# CCLights.net
KiCad netlist of a schematic drawn in Altium Designer
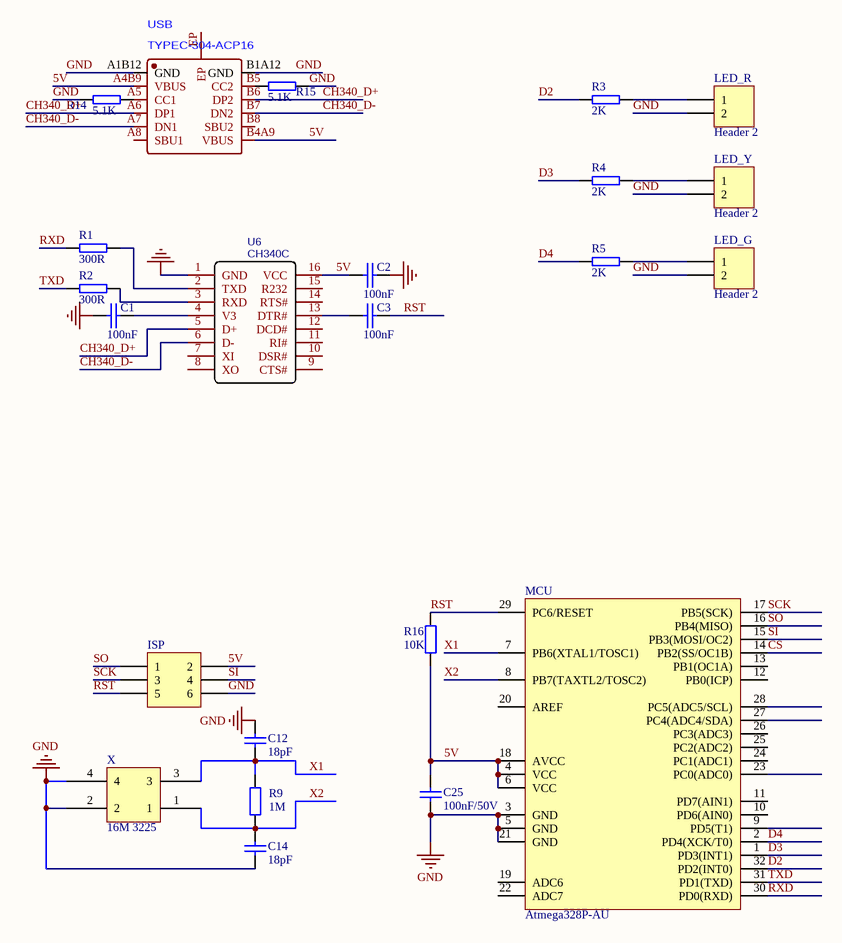
[diagram p0: CCLights.schdoc]

(export (version "E")
  (design (tool "Eeschema 10.0.6"))
  (components
    (comp (ref "C1")
      (value "100nF")
      (footprint "Miscellaneous Devices LC:LC-0603_C")
      (description "Capacitor")
      (libsource (lib "*") (part "CAP"))
    )
    (comp (ref "C2")
      (value "100nF")
      (footprint "Miscellaneous Devices LC:LC-0603_C")
      (description "Capacitor")
      (libsource (lib "*") (part "CAP"))
    )
    (comp (ref "C3")
      (value "100nF")
      (footprint "Miscellaneous Devices LC:LC-0603_C")
      (description "Capacitor")
      (libsource (lib "*") (part "CAP"))
    )
    (comp (ref "C12")
      (value "18pF")
      (footprint "0603C")
      (description "Capacitor")
      (fields (field (name "PUBLISHER") "Altium Limited"))
      (libsource (lib "Miscellaneous Devices") (part "Cap"))
    )
    (comp (ref "C14")
      (value "18pF")
      (footprint "0603C")
      (description "Capacitor")
      (fields (field (name "PUBLISHER") "Altium Limited"))
      (libsource (lib "Miscellaneous Devices") (part "Cap"))
    )
    (comp (ref "C25")
      (value "100nF/50V")
      (footprint "LC-0603_C")
      (description "Capacitor")
      (fields (field (name "PUBLISHER") "Altium Limited"))
      (libsource (lib "Miscellaneous Devices") (part "Cap"))
    )
    (comp (ref "ISP")
      (value "Header 3X2")
      (footprint "HDR2X3")
      (description "Header, 3-Pin, Dual row")
      (fields (field (name "PUBLISHER") "Altium Limited"))
      (libsource (lib "Miscellaneous Connectors") (part "Header 3X2"))
    )
    (comp (ref "LED_G")
      (value "Header 2")
      (footprint "HDR1X2")
      (description "Header, 2-Pin")
      (fields (field (name "PUBLISHER") "Altium Limited"))
      (libsource (lib "Miscellaneous Connectors") (part "Header 2"))
    )
    (comp (ref "LED_R")
      (value "Header 2")
      (footprint "HDR1X2")
      (description "Header, 2-Pin")
      (fields (field (name "PUBLISHER") "Altium Limited"))
      (libsource (lib "Miscellaneous Connectors") (part "Header 2"))
    )
    (comp (ref "LED_Y")
      (value "Header 2")
      (footprint "HDR1X2")
      (description "Header, 2-Pin")
      (fields (field (name "PUBLISHER") "Altium Limited"))
      (libsource (lib "Miscellaneous Connectors") (part "Header 2"))
    )
    (comp (ref "MCU")
      (value "Atmega328P-AU")
      (footprint "LQFP32")
      (libsource (lib "表贴元件") (part "Atmega328P-AU"))
    )
    (comp (ref "R1")
      (value "300R")
      (footprint "Miscellaneous Devices LC:LC-0603_R")
      (libsource (lib "*") (part "RES2"))
    )
    (comp (ref "R2")
      (value "300R")
      (footprint "Miscellaneous Devices LC:LC-0603_R")
      (libsource (lib "*") (part "RES2"))
    )
    (comp (ref "R3")
      (value "2K")
      (footprint "Miscellaneous Devices LC:LC-0603_R")
      (libsource (lib "*") (part "RES2"))
    )
    (comp (ref "R4")
      (value "2K")
      (footprint "Miscellaneous Devices LC:LC-0603_R")
      (libsource (lib "*") (part "RES2"))
    )
    (comp (ref "R5")
      (value "2K")
      (footprint "Miscellaneous Devices LC:LC-0603_R")
      (libsource (lib "*") (part "RES2"))
    )
    (comp (ref "R9")
      (value "1M")
      (footprint "0603R")
      (description "Resistor")
      (fields (field (name "PUBLISHER") "Altium Limited"))
      (libsource (lib "Miscellaneous Devices") (part "Res2"))
    )
    (comp (ref "R14")
      (value "5.1K")
      (footprint "Miscellaneous Devices LC:LC-0402_R")
      (libsource (lib "*") (part "RES2"))
    )
    (comp (ref "R15")
      (value "5.1K")
      (footprint "Miscellaneous Devices LC:LC-0402_R")
      (libsource (lib "*") (part "RES2"))
    )
    (comp (ref "R16")
      (value "10K")
      (footprint "0603R")
      (description "Resistor")
      (fields (field (name "PUBLISHER") "Altium Limited"))
      (libsource (lib "Miscellaneous Devices") (part "Res2"))
    )
    (comp (ref "U6")
      (value "CH340C")
      (footprint "SOP-16_L10.0-W3.9-P1.27-LS6.0-BL")
      (fields (field (name "BOM_SUPPLIER PART") "C84681"))
      (libsource (lib "altium-import") (part "root_0_CH340C_"))
    )
    (comp (ref "USB")
      (value "TYPEC-304-ACP16")
      (footprint "USB-C-SMD_TYPE-C-16P-1")
      (libsource (lib "altium-import") (part "root_0_TYPEC-304-ACP16_"))
    )
    (comp (ref "X")
      (value "16M 3225")
      (footprint "Miscellaneous Devices LC:LC-SMD-3225_4P")
      (description "16M_SMD_3225")
      (libsource (lib "16M_SMD_3225") (part "Component_1"))
    )
  )
  (nets
    (net (code "1") (name "/5V") (class "Default")
      (node (ref "C2") (pin "1") (pinfunction "1_1") (pintype "passive"))
      (node (ref "C25") (pin "2") (pinfunction "2_2") (pintype "passive"))
      (node (ref "ISP") (pin "2") (pinfunction "2_2") (pintype "passive"))
      (node (ref "MCU") (pin "18") (pinfunction "AVCC_18") (pintype "passive"))
      (node (ref "MCU") (pin "4") (pinfunction "VCC_4") (pintype "passive"))
      (node (ref "MCU") (pin "6") (pinfunction "VCC_6") (pintype "passive"))
      (node (ref "R16") (pin "2") (pinfunction "2_2") (pintype "passive"))
      (node (ref "U6") (pin "16") (pinfunction "VCC_16") (pintype "passive"))
      (node (ref "USB") (pin "A4B9") (pinfunction "VBUS_A4B9") (pintype "passive"))
      (node (ref "USB") (pin "B4A9") (pinfunction "VBUS_B4A9") (pintype "passive"))
    )
    (net (code "2") (name "/CH340_D+") (class "Default")
      (node (ref "U6") (pin "5") (pinfunction "D+_5") (pintype "passive"))
      (node (ref "USB") (pin "A6") (pinfunction "DP1_A6") (pintype "passive"))
      (node (ref "USB") (pin "B6") (pinfunction "DP2_B6") (pintype "passive"))
    )
    (net (code "3") (name "/CH340_D-") (class "Default")
      (node (ref "U6") (pin "6") (pinfunction "D-_6") (pintype "passive"))
      (node (ref "USB") (pin "A7") (pinfunction "DN1_A7") (pintype "passive"))
      (node (ref "USB") (pin "B7") (pinfunction "DN2_B7") (pintype "passive"))
    )
    (net (code "4") (name "/CS") (class "Default")
      (node (ref "MCU") (pin "14") (pinfunction "PB2(SS/OC1B)_14") (pintype "passive"))
    )
    (net (code "5") (name "/D2") (class "Default")
      (node (ref "MCU") (pin "32") (pinfunction "PD2(INT0)_32") (pintype "passive"))
      (node (ref "R3") (pin "2") (pinfunction "2_2") (pintype "passive"))
    )
    (net (code "6") (name "/D3") (class "Default")
      (node (ref "MCU") (pin "1") (pinfunction "PD3(INT1)_1") (pintype "passive"))
      (node (ref "R4") (pin "2") (pinfunction "2_2") (pintype "passive"))
    )
    (net (code "7") (name "/D4") (class "Default")
      (node (ref "MCU") (pin "2") (pinfunction "PD4(XCK/T0)_2") (pintype "passive"))
      (node (ref "R5") (pin "2") (pinfunction "2_2") (pintype "passive"))
    )
    (net (code "8") (name "/RST") (class "Default")
      (node (ref "C3") (pin "2") (pinfunction "2_2") (pintype "passive"))
      (node (ref "ISP") (pin "5") (pinfunction "5_5") (pintype "passive"))
      (node (ref "MCU") (pin "29") (pinfunction "PC6/RESET_29") (pintype "passive"))
      (node (ref "R16") (pin "1") (pinfunction "1_1") (pintype "passive"))
    )
    (net (code "9") (name "/RXD") (class "Default")
      (node (ref "MCU") (pin "30") (pinfunction "PD0(RXD)_30") (pintype "passive"))
      (node (ref "R1") (pin "2") (pinfunction "2_2") (pintype "passive"))
    )
    (net (code "10") (name "/SCK") (class "Default")
      (node (ref "ISP") (pin "3") (pinfunction "3_3") (pintype "passive"))
      (node (ref "MCU") (pin "17") (pinfunction "PB5(SCK)_17") (pintype "passive"))
    )
    (net (code "11") (name "/SI") (class "Default")
      (node (ref "ISP") (pin "4") (pinfunction "4_4") (pintype "passive"))
      (node (ref "MCU") (pin "15") (pinfunction "PB3(MOSI/OC2)_15") (pintype "passive"))
    )
    (net (code "12") (name "/SO") (class "Default")
      (node (ref "ISP") (pin "1") (pinfunction "1_1") (pintype "passive"))
      (node (ref "MCU") (pin "16") (pinfunction "PB4(MISO)_16") (pintype "passive"))
    )
    (net (code "13") (name "/TXD") (class "Default")
      (node (ref "MCU") (pin "31") (pinfunction "PD1(TXD)_31") (pintype "passive"))
      (node (ref "R2") (pin "2") (pinfunction "2_2") (pintype "passive"))
    )
    (net (code "14") (name "/X1") (class "Default")
      (node (ref "C12") (pin "2") (pinfunction "2_2") (pintype "passive"))
      (node (ref "MCU") (pin "7") (pinfunction "PB6(XTAL1/TOSC1)_7") (pintype "passive"))
      (node (ref "R9") (pin "1") (pinfunction "1_1") (pintype "passive"))
      (node (ref "X") (pin "3") (pinfunction "3_3") (pintype "passive"))
    )
    (net (code "15") (name "/X2") (class "Default")
      (node (ref "C14") (pin "1") (pinfunction "1_1") (pintype "passive"))
      (node (ref "MCU") (pin "8") (pinfunction "PB7(TAXTL2/TOSC2)_8") (pintype "passive"))
      (node (ref "R9") (pin "2") (pinfunction "2_2") (pintype "passive"))
      (node (ref "X") (pin "1") (pinfunction "1_1") (pintype "passive"))
    )
    (net (code "16") (name "GND") (class "Default")
      (node (ref "C1") (pin "1") (pinfunction "1_1") (pintype "passive"))
      (node (ref "C12") (pin "1") (pinfunction "1_1") (pintype "passive"))
      (node (ref "C14") (pin "2") (pinfunction "2_2") (pintype "passive"))
      (node (ref "C2") (pin "2") (pinfunction "2_2") (pintype "passive"))
      (node (ref "C25") (pin "1") (pinfunction "1_1") (pintype "passive"))
      (node (ref "ISP") (pin "6") (pinfunction "6_6") (pintype "passive"))
      (node (ref "LED_G") (pin "2") (pinfunction "2_2") (pintype "passive"))
      (node (ref "LED_R") (pin "2") (pinfunction "2_2") (pintype "passive"))
      (node (ref "LED_Y") (pin "2") (pinfunction "2_2") (pintype "passive"))
      (node (ref "MCU") (pin "21") (pinfunction "GND_21") (pintype "passive"))
      (node (ref "MCU") (pin "3") (pinfunction "GND_3") (pintype "passive"))
      (node (ref "MCU") (pin "5") (pinfunction "GND_5") (pintype "passive"))
      (node (ref "R14") (pin "1") (pinfunction "1_1") (pintype "passive"))
      (node (ref "R15") (pin "2") (pinfunction "2_2") (pintype "passive"))
      (node (ref "U6") (pin "1") (pinfunction "GND_1") (pintype "passive"))
      (node (ref "USB") (pin "A1B12") (pinfunction "GND_A1B12") (pintype "passive"))
      (node (ref "USB") (pin "B1A12") (pinfunction "GND_B1A12") (pintype "passive"))
      (node (ref "X") (pin "2") (pinfunction "2_2") (pintype "passive"))
      (node (ref "X") (pin "4") (pinfunction "4_4") (pintype "passive"))
    )
    (net (code "17") (name "Net-(LED_G-Pad1)") (class "Default")
      (node (ref "LED_G") (pin "1") (pinfunction "1_1") (pintype "passive"))
      (node (ref "R5") (pin "1") (pinfunction "1_1") (pintype "passive"))
    )
    (net (code "18") (name "Net-(LED_R-Pad1)") (class "Default")
      (node (ref "LED_R") (pin "1") (pinfunction "1_1") (pintype "passive"))
      (node (ref "R3") (pin "1") (pinfunction "1_1") (pintype "passive"))
    )
    (net (code "19") (name "Net-(LED_Y-Pad1)") (class "Default")
      (node (ref "LED_Y") (pin "1") (pinfunction "1_1") (pintype "passive"))
      (node (ref "R4") (pin "1") (pinfunction "1_1") (pintype "passive"))
    )
    (net (code "20") (name "Net-(U6-DTR#)") (class "Default")
      (node (ref "C3") (pin "1") (pinfunction "1_1") (pintype "passive"))
      (node (ref "U6") (pin "13") (pinfunction "DTR#_13") (pintype "passive"))
    )
    (net (code "21") (name "Net-(U6-RXD)") (class "Default")
      (node (ref "R2") (pin "1") (pinfunction "1_1") (pintype "passive"))
      (node (ref "U6") (pin "3") (pinfunction "RXD_3") (pintype "passive"))
    )
    (net (code "22") (name "Net-(U6-TXD)") (class "Default")
      (node (ref "R1") (pin "1") (pinfunction "1_1") (pintype "passive"))
      (node (ref "U6") (pin "2") (pinfunction "TXD_2") (pintype "passive"))
    )
    (net (code "23") (name "Net-(U6-V3)") (class "Default")
      (node (ref "C1") (pin "2") (pinfunction "2_2") (pintype "passive"))
      (node (ref "U6") (pin "4") (pinfunction "V3_4") (pintype "passive"))
    )
    (net (code "24") (name "Net-(USB-CC1)") (class "Default")
      (node (ref "R14") (pin "2") (pinfunction "2_2") (pintype "passive"))
      (node (ref "USB") (pin "A5") (pinfunction "CC1_A5") (pintype "passive"))
    )
    (net (code "25") (name "Net-(USB-CC2)") (class "Default")
      (node (ref "R15") (pin "1") (pinfunction "1_1") (pintype "passive"))
      (node (ref "USB") (pin "B5") (pinfunction "CC2_B5") (pintype "passive"))
    )
    (net (code "26") (name "unconnected-(MCU-ADC6-Pad19)") (class "Default")
      (node (ref "MCU") (pin "19") (pinfunction "ADC6_19") (pintype "passive"))
    )
    (net (code "27") (name "unconnected-(MCU-ADC7-Pad22)") (class "Default")
      (node (ref "MCU") (pin "22") (pinfunction "ADC7_22") (pintype "passive"))
    )
    (net (code "28") (name "unconnected-(MCU-AREF-Pad20)") (class "Default")
      (node (ref "MCU") (pin "20") (pinfunction "AREF_20") (pintype "passive"))
    )
    (net (code "29") (name "unconnected-(MCU-PB0(ICP)-Pad12)") (class "Default")
      (node (ref "MCU") (pin "12") (pinfunction "PB0(ICP)_12") (pintype "passive"))
    )
    (net (code "30") (name "unconnected-(MCU-PB1(OC1A)-Pad13)") (class "Default")
      (node (ref "MCU") (pin "13") (pinfunction "PB1(OC1A)_13") (pintype "passive"))
    )
    (net (code "31") (name "unconnected-(MCU-PC0(ADC0)-Pad23)") (class "Default")
      (node (ref "MCU") (pin "23") (pinfunction "PC0(ADC0)_23") (pintype "passive"))
    )
    (net (code "32") (name "unconnected-(MCU-PC1(ADC1)-Pad24)") (class "Default")
      (node (ref "MCU") (pin "24") (pinfunction "PC1(ADC1)_24") (pintype "passive"))
    )
    (net (code "33") (name "unconnected-(MCU-PC2(ADC2)-Pad25)") (class "Default")
      (node (ref "MCU") (pin "25") (pinfunction "PC2(ADC2)_25") (pintype "passive"))
    )
    (net (code "34") (name "unconnected-(MCU-PC3(ADC3)-Pad26)") (class "Default")
      (node (ref "MCU") (pin "26") (pinfunction "PC3(ADC3)_26") (pintype "passive"))
    )
    (net (code "35") (name "unconnected-(MCU-PC4(ADC4{slash}SDA)-Pad27)") (class "Default")
      (node (ref "MCU") (pin "27") (pinfunction "PC4(ADC4/SDA)_27") (pintype "passive"))
    )
    (net (code "36") (name "unconnected-(MCU-PC5(ADC5{slash}SCL)-Pad28)") (class "Default")
      (node (ref "MCU") (pin "28") (pinfunction "PC5(ADC5/SCL)_28") (pintype "passive"))
    )
    (net (code "37") (name "unconnected-(MCU-PD5(T1)-Pad9)") (class "Default")
      (node (ref "MCU") (pin "9") (pinfunction "PD5(T1)_9") (pintype "passive"))
    )
    (net (code "38") (name "unconnected-(MCU-PD6(AIN0)-Pad10)") (class "Default")
      (node (ref "MCU") (pin "10") (pinfunction "PD6(AIN0)_10") (pintype "passive"))
    )
    (net (code "39") (name "unconnected-(MCU-PD7(AIN1)-Pad11)") (class "Default")
      (node (ref "MCU") (pin "11") (pinfunction "PD7(AIN1)_11") (pintype "passive"))
    )
    (net (code "40") (name "unconnected-(U6-CTS#-Pad9)") (class "Default")
      (node (ref "U6") (pin "9") (pinfunction "CTS#_9") (pintype "passive"))
    )
    (net (code "41") (name "unconnected-(U6-DCD#-Pad12)") (class "Default")
      (node (ref "U6") (pin "12") (pinfunction "DCD#_12") (pintype "passive"))
    )
    (net (code "42") (name "unconnected-(U6-DSR#-Pad10)") (class "Default")
      (node (ref "U6") (pin "10") (pinfunction "DSR#_10") (pintype "passive"))
    )
    (net (code "43") (name "unconnected-(U6-R232-Pad15)") (class "Default")
      (node (ref "U6") (pin "15") (pinfunction "R232_15") (pintype "passive"))
    )
    (net (code "44") (name "unconnected-(U6-RI#-Pad11)") (class "Default")
      (node (ref "U6") (pin "11") (pinfunction "RI#_11") (pintype "passive"))
    )
    (net (code "45") (name "unconnected-(U6-RTS#-Pad14)") (class "Default")
      (node (ref "U6") (pin "14") (pinfunction "RTS#_14") (pintype "passive"))
    )
    (net (code "46") (name "unconnected-(U6-XI-Pad7)") (class "Default")
      (node (ref "U6") (pin "7") (pinfunction "XI_7") (pintype "passive"))
    )
    (net (code "47") (name "unconnected-(U6-XO-Pad8)") (class "Default")
      (node (ref "U6") (pin "8") (pinfunction "XO_8") (pintype "passive"))
    )
    (net (code "48") (name "unconnected-(USB-PadEP)") (class "Default")
      (node (ref "USB") (pin "EP") (pinfunction "EP_EP") (pintype "passive"))
    )
    (net (code "49") (name "unconnected-(USB-SBU1-PadA8)") (class "Default")
      (node (ref "USB") (pin "A8") (pinfunction "SBU1_A8") (pintype "passive"))
    )
    (net (code "50") (name "unconnected-(USB-SBU2-PadB8)") (class "Default")
      (node (ref "USB") (pin "B8") (pinfunction "SBU2_B8") (pintype "passive"))
    )
  )
)
